# clock-temp-touch.net
KiCad netlist of a schematic drawn in Altium Designer
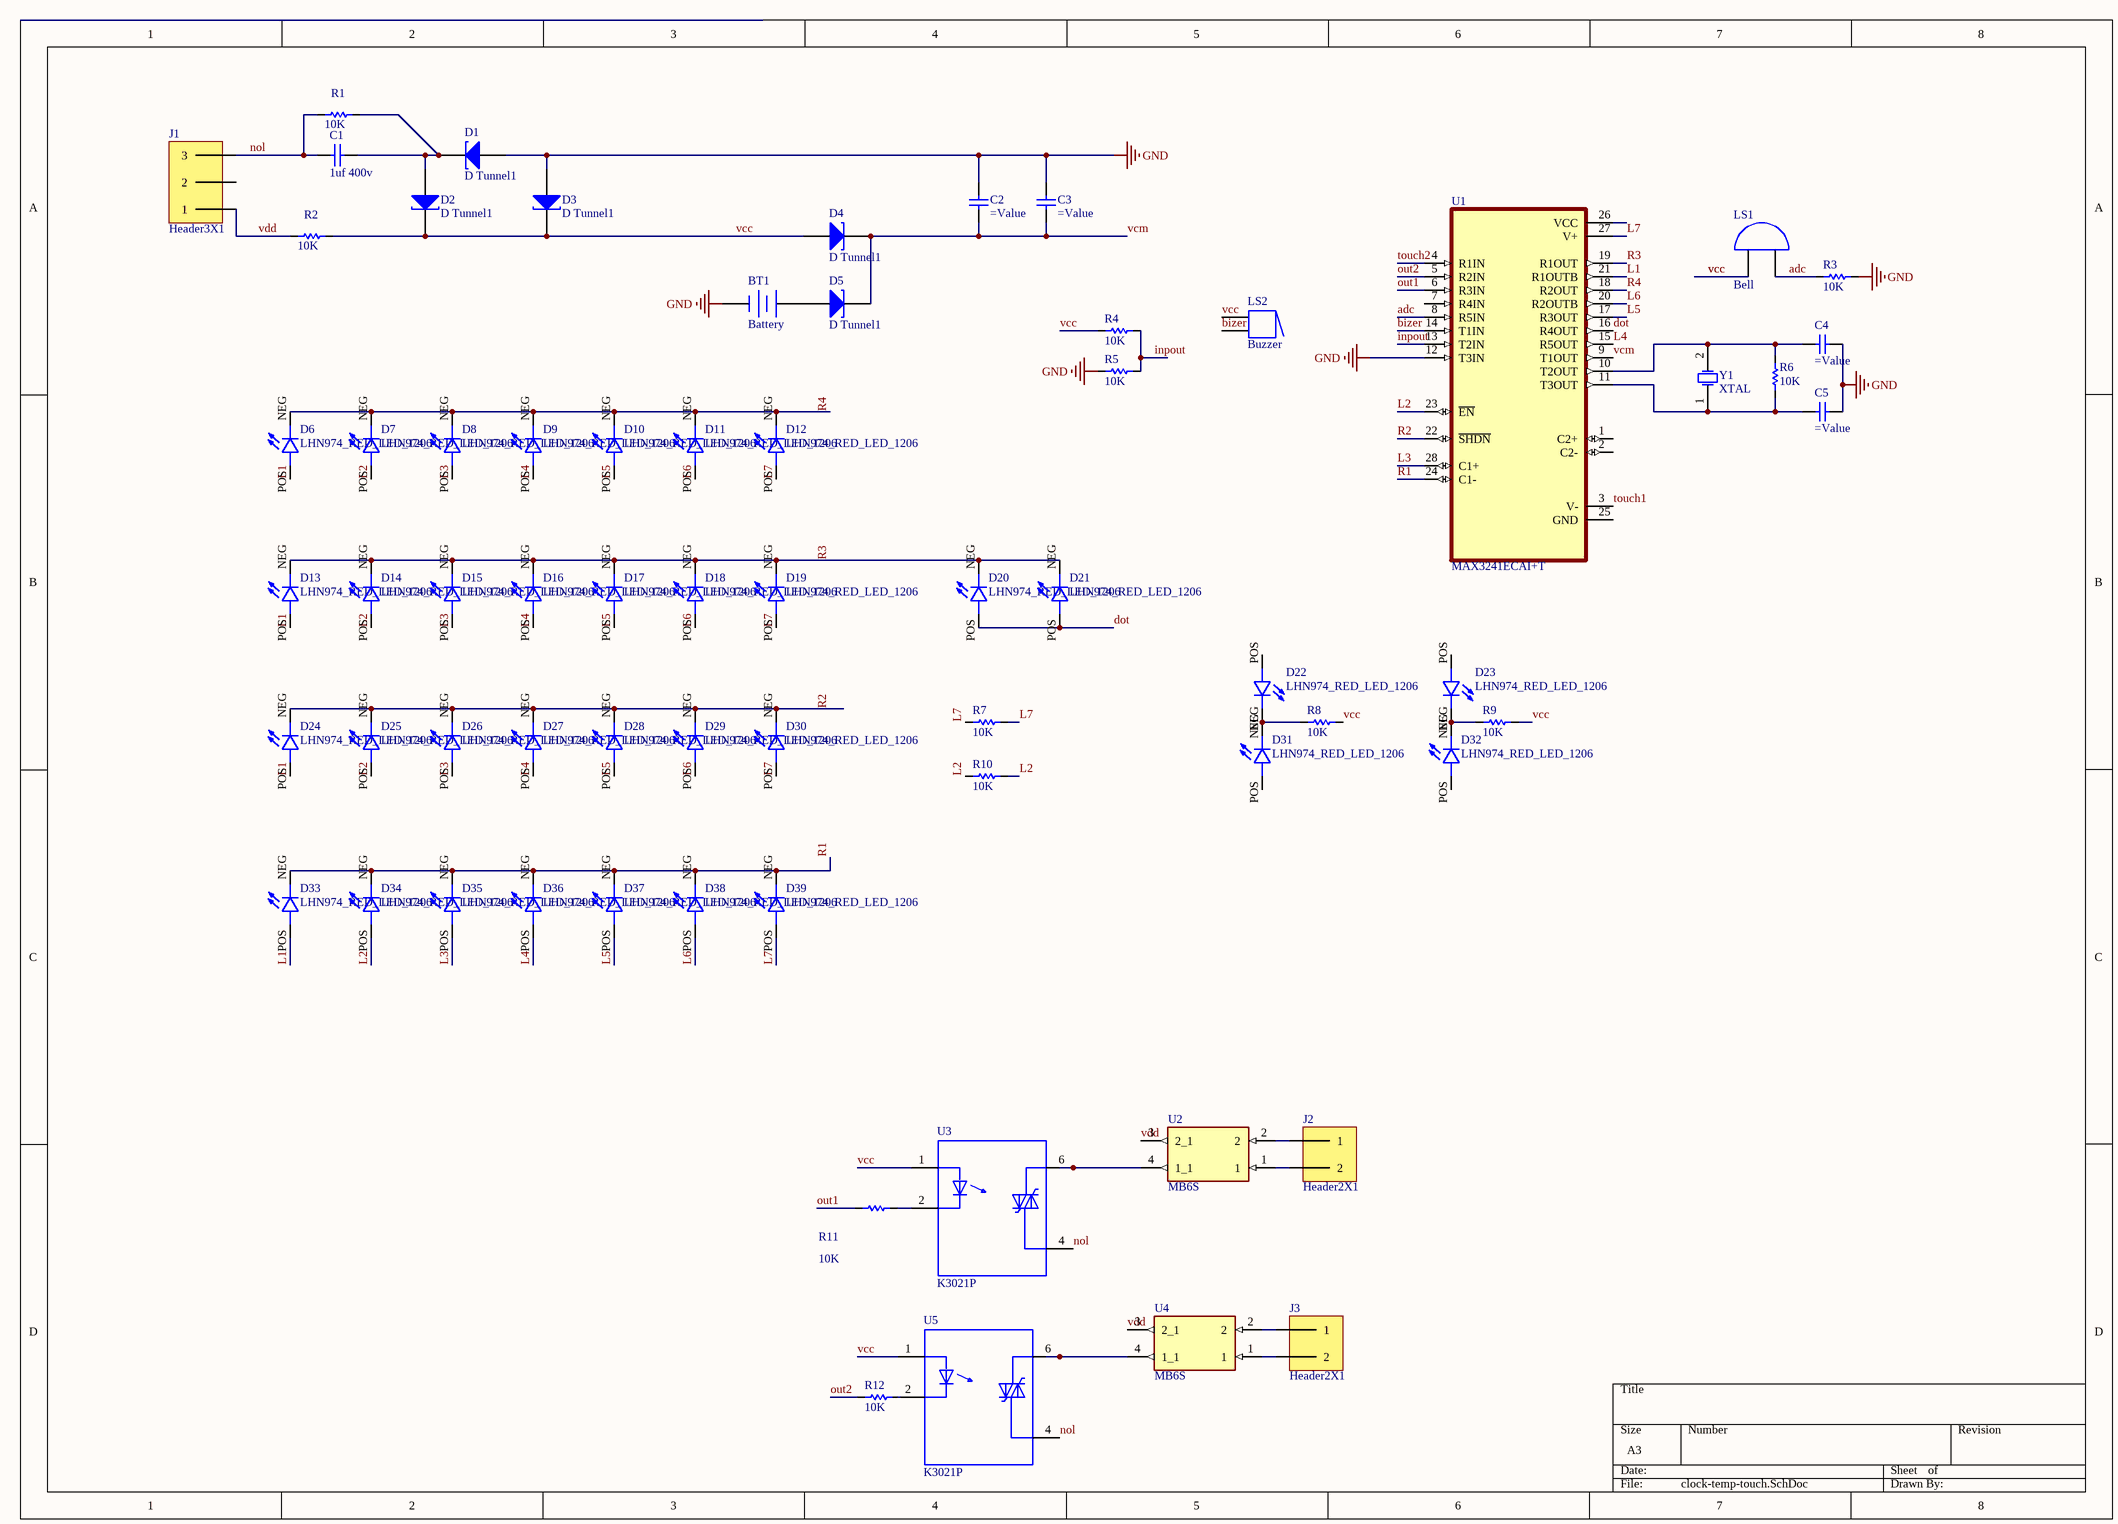
[diagram p0: clock-temp-touch.SchDoc]

(export (version "E")
  (design (tool "Eeschema 10.0.6"))
  (components
    (comp (ref "BT1")
      (value "Battery")
      (footprint "BAT-2")
      (description "Multicell Battery")
      (fields (field (name "PUBLISHER") "Altium Limited"))
      (libsource (lib "Miscellaneous Devices") (part "Battery"))
    )
    (comp (ref "C1")
      (value "1uf 400v")
      (footprint "1uf 400v")
      (description "Capacitor 24*9mm")
      (fields (field (name "DESIGNER") "Seyed Mohsen Ghasemain"))
      (libsource (lib "PicPars.com_usefully_Library") (part "1uf 400v"))
    )
    (comp (ref "C2")
      (value "~")
      (footprint "CAP 1206")
      (description "Capacitor")
      (libsource (lib "AltiumLib1") (part "Capacitor"))
    )
    (comp (ref "C3")
      (value "~")
      (footprint "CAP 1206")
      (description "Capacitor")
      (libsource (lib "AltiumLib1") (part "Capacitor"))
    )
    (comp (ref "C4")
      (value "~")
      (footprint "CAP 1206")
      (description "Capacitor")
      (libsource (lib "AltiumLib1") (part "Capacitor"))
    )
    (comp (ref "C5")
      (value "~")
      (footprint "CAP 1206")
      (description "Capacitor")
      (libsource (lib "AltiumLib1") (part "Capacitor"))
    )
    (comp (ref "D1")
      (value "D Tunnel1")
      (footprint "3.2X1.6X1.1")
      (description "Tunnel Diode - RLC Model")
      (fields (field (name "PUBLISHER") "Altium Limited"))
      (libsource (lib "Miscellaneous Devices") (part "D Tunnel1"))
    )
    (comp (ref "D2")
      (value "D Tunnel1")
      (footprint "3.2X1.6X1.1")
      (description "Tunnel Diode - RLC Model")
      (fields (field (name "PUBLISHER") "Altium Limited"))
      (libsource (lib "Miscellaneous Devices") (part "D Tunnel1"))
    )
    (comp (ref "D3")
      (value "D Tunnel1")
      (footprint "3.2X1.6X1.1")
      (description "Tunnel Diode - RLC Model")
      (fields (field (name "PUBLISHER") "Altium Limited"))
      (libsource (lib "Miscellaneous Devices") (part "D Tunnel1"))
    )
    (comp (ref "D4")
      (value "D Tunnel1")
      (footprint "3.2X1.6X1.1")
      (description "Tunnel Diode - RLC Model")
      (fields (field (name "PUBLISHER") "Altium Limited"))
      (libsource (lib "Miscellaneous Devices") (part "D Tunnel1"))
    )
    (comp (ref "D5")
      (value "D Tunnel1")
      (footprint "3.2X1.6X1.1")
      (description "Tunnel Diode - RLC Model")
      (fields (field (name "PUBLISHER") "Altium Limited"))
      (libsource (lib "Miscellaneous Devices") (part "D Tunnel1"))
    )
    (comp (ref "D6")
      (value "LHN974_RED_LED_1206")
      (footprint "LEDC3216X120N")
      (description "2.6 V Red LED SMD")
      (fields (field (name "MP") "LHN974 RED LED 1206") (field (name "MF") "Osram"))
      (libsource (lib "LHN974_RED_LED_1206") (part "LHN974_RED_LED_1206"))
    )
    (comp (ref "D7")
      (value "LHN974_RED_LED_1206")
      (footprint "LEDC3216X120N")
      (description "2.6 V Red LED SMD")
      (fields (field (name "MP") "LHN974 RED LED 1206") (field (name "MF") "Osram"))
      (libsource (lib "LHN974_RED_LED_1206") (part "LHN974_RED_LED_1206"))
    )
    (comp (ref "D8")
      (value "LHN974_RED_LED_1206")
      (footprint "LEDC3216X120N")
      (description "2.6 V Red LED SMD")
      (fields (field (name "MP") "LHN974 RED LED 1206") (field (name "MF") "Osram"))
      (libsource (lib "LHN974_RED_LED_1206") (part "LHN974_RED_LED_1206"))
    )
    (comp (ref "D9")
      (value "LHN974_RED_LED_1206")
      (footprint "LEDC3216X120N")
      (description "2.6 V Red LED SMD")
      (fields (field (name "MP") "LHN974 RED LED 1206") (field (name "MF") "Osram"))
      (libsource (lib "LHN974_RED_LED_1206") (part "LHN974_RED_LED_1206"))
    )
    (comp (ref "D10")
      (value "LHN974_RED_LED_1206")
      (footprint "LEDC3216X120N")
      (description "2.6 V Red LED SMD")
      (fields (field (name "MP") "LHN974 RED LED 1206") (field (name "MF") "Osram"))
      (libsource (lib "LHN974_RED_LED_1206") (part "LHN974_RED_LED_1206"))
    )
    (comp (ref "D11")
      (value "LHN974_RED_LED_1206")
      (footprint "LEDC3216X120N")
      (description "2.6 V Red LED SMD")
      (fields (field (name "MP") "LHN974 RED LED 1206") (field (name "MF") "Osram"))
      (libsource (lib "LHN974_RED_LED_1206") (part "LHN974_RED_LED_1206"))
    )
    (comp (ref "D12")
      (value "LHN974_RED_LED_1206")
      (footprint "LEDC3216X120N")
      (description "2.6 V Red LED SMD")
      (fields (field (name "MP") "LHN974 RED LED 1206") (field (name "MF") "Osram"))
      (libsource (lib "LHN974_RED_LED_1206") (part "LHN974_RED_LED_1206"))
    )
    (comp (ref "D13")
      (value "LHN974_RED_LED_1206")
      (footprint "LEDC3216X120N")
      (description "2.6 V Red LED SMD")
      (fields (field (name "MP") "LHN974 RED LED 1206") (field (name "MF") "Osram"))
      (libsource (lib "LHN974_RED_LED_1206") (part "LHN974_RED_LED_1206"))
    )
    (comp (ref "D14")
      (value "LHN974_RED_LED_1206")
      (footprint "LEDC3216X120N")
      (description "2.6 V Red LED SMD")
      (fields (field (name "MP") "LHN974 RED LED 1206") (field (name "MF") "Osram"))
      (libsource (lib "LHN974_RED_LED_1206") (part "LHN974_RED_LED_1206"))
    )
    (comp (ref "D15")
      (value "LHN974_RED_LED_1206")
      (footprint "LEDC3216X120N")
      (description "2.6 V Red LED SMD")
      (fields (field (name "MP") "LHN974 RED LED 1206") (field (name "MF") "Osram"))
      (libsource (lib "LHN974_RED_LED_1206") (part "LHN974_RED_LED_1206"))
    )
    (comp (ref "D16")
      (value "LHN974_RED_LED_1206")
      (footprint "LEDC3216X120N")
      (description "2.6 V Red LED SMD")
      (fields (field (name "MP") "LHN974 RED LED 1206") (field (name "MF") "Osram"))
      (libsource (lib "LHN974_RED_LED_1206") (part "LHN974_RED_LED_1206"))
    )
    (comp (ref "D17")
      (value "LHN974_RED_LED_1206")
      (footprint "LEDC3216X120N")
      (description "2.6 V Red LED SMD")
      (fields (field (name "MP") "LHN974 RED LED 1206") (field (name "MF") "Osram"))
      (libsource (lib "LHN974_RED_LED_1206") (part "LHN974_RED_LED_1206"))
    )
    (comp (ref "D18")
      (value "LHN974_RED_LED_1206")
      (footprint "LEDC3216X120N")
      (description "2.6 V Red LED SMD")
      (fields (field (name "MP") "LHN974 RED LED 1206") (field (name "MF") "Osram"))
      (libsource (lib "LHN974_RED_LED_1206") (part "LHN974_RED_LED_1206"))
    )
    (comp (ref "D19")
      (value "LHN974_RED_LED_1206")
      (footprint "LEDC3216X120N")
      (description "2.6 V Red LED SMD")
      (fields (field (name "MP") "LHN974 RED LED 1206") (field (name "MF") "Osram"))
      (libsource (lib "LHN974_RED_LED_1206") (part "LHN974_RED_LED_1206"))
    )
    (comp (ref "D20")
      (value "LHN974_RED_LED_1206")
      (footprint "LEDC3216X120N")
      (description "2.6 V Red LED SMD")
      (fields (field (name "MP") "LHN974 RED LED 1206") (field (name "MF") "Osram"))
      (libsource (lib "LHN974_RED_LED_1206") (part "LHN974_RED_LED_1206"))
    )
    (comp (ref "D21")
      (value "LHN974_RED_LED_1206")
      (footprint "LEDC3216X120N")
      (description "2.6 V Red LED SMD")
      (fields (field (name "MP") "LHN974 RED LED 1206") (field (name "MF") "Osram"))
      (libsource (lib "LHN974_RED_LED_1206") (part "LHN974_RED_LED_1206"))
    )
    (comp (ref "D22")
      (value "LHN974_RED_LED_1206")
      (footprint "LEDC3216X120N")
      (description "2.6 V Red LED SMD")
      (fields (field (name "MP") "LHN974 RED LED 1206") (field (name "MF") "Osram"))
      (libsource (lib "LHN974_RED_LED_1206") (part "LHN974_RED_LED_1206"))
    )
    (comp (ref "D23")
      (value "LHN974_RED_LED_1206")
      (footprint "LEDC3216X120N")
      (description "2.6 V Red LED SMD")
      (fields (field (name "MP") "LHN974 RED LED 1206") (field (name "MF") "Osram"))
      (libsource (lib "LHN974_RED_LED_1206") (part "LHN974_RED_LED_1206"))
    )
    (comp (ref "D24")
      (value "LHN974_RED_LED_1206")
      (footprint "LEDC3216X120N")
      (description "2.6 V Red LED SMD")
      (fields (field (name "MP") "LHN974 RED LED 1206") (field (name "MF") "Osram"))
      (libsource (lib "LHN974_RED_LED_1206") (part "LHN974_RED_LED_1206"))
    )
    (comp (ref "D25")
      (value "LHN974_RED_LED_1206")
      (footprint "LEDC3216X120N")
      (description "2.6 V Red LED SMD")
      (fields (field (name "MP") "LHN974 RED LED 1206") (field (name "MF") "Osram"))
      (libsource (lib "LHN974_RED_LED_1206") (part "LHN974_RED_LED_1206"))
    )
    (comp (ref "D26")
      (value "LHN974_RED_LED_1206")
      (footprint "LEDC3216X120N")
      (description "2.6 V Red LED SMD")
      (fields (field (name "MP") "LHN974 RED LED 1206") (field (name "MF") "Osram"))
      (libsource (lib "LHN974_RED_LED_1206") (part "LHN974_RED_LED_1206"))
    )
    (comp (ref "D27")
      (value "LHN974_RED_LED_1206")
      (footprint "LEDC3216X120N")
      (description "2.6 V Red LED SMD")
      (fields (field (name "MP") "LHN974 RED LED 1206") (field (name "MF") "Osram"))
      (libsource (lib "LHN974_RED_LED_1206") (part "LHN974_RED_LED_1206"))
    )
    (comp (ref "D28")
      (value "LHN974_RED_LED_1206")
      (footprint "LEDC3216X120N")
      (description "2.6 V Red LED SMD")
      (fields (field (name "MP") "LHN974 RED LED 1206") (field (name "MF") "Osram"))
      (libsource (lib "LHN974_RED_LED_1206") (part "LHN974_RED_LED_1206"))
    )
    (comp (ref "D29")
      (value "LHN974_RED_LED_1206")
      (footprint "LEDC3216X120N")
      (description "2.6 V Red LED SMD")
      (fields (field (name "MP") "LHN974 RED LED 1206") (field (name "MF") "Osram"))
      (libsource (lib "LHN974_RED_LED_1206") (part "LHN974_RED_LED_1206"))
    )
    (comp (ref "D30")
      (value "LHN974_RED_LED_1206")
      (footprint "LEDC3216X120N")
      (description "2.6 V Red LED SMD")
      (fields (field (name "MP") "LHN974 RED LED 1206") (field (name "MF") "Osram"))
      (libsource (lib "LHN974_RED_LED_1206") (part "LHN974_RED_LED_1206"))
    )
    (comp (ref "D31")
      (value "LHN974_RED_LED_1206")
      (footprint "LEDC3216X120N")
      (description "2.6 V Red LED SMD")
      (fields (field (name "MP") "LHN974 RED LED 1206") (field (name "MF") "Osram"))
      (libsource (lib "LHN974_RED_LED_1206") (part "LHN974_RED_LED_1206"))
    )
    (comp (ref "D32")
      (value "LHN974_RED_LED_1206")
      (footprint "LEDC3216X120N")
      (description "2.6 V Red LED SMD")
      (fields (field (name "MP") "LHN974 RED LED 1206") (field (name "MF") "Osram"))
      (libsource (lib "LHN974_RED_LED_1206") (part "LHN974_RED_LED_1206"))
    )
    (comp (ref "D33")
      (value "LHN974_RED_LED_1206")
      (footprint "LEDC3216X120N")
      (description "2.6 V Red LED SMD")
      (fields (field (name "MP") "LHN974 RED LED 1206") (field (name "MF") "Osram"))
      (libsource (lib "LHN974_RED_LED_1206") (part "LHN974_RED_LED_1206"))
    )
    (comp (ref "D34")
      (value "LHN974_RED_LED_1206")
      (footprint "LEDC3216X120N")
      (description "2.6 V Red LED SMD")
      (fields (field (name "MP") "LHN974 RED LED 1206") (field (name "MF") "Osram"))
      (libsource (lib "LHN974_RED_LED_1206") (part "LHN974_RED_LED_1206"))
    )
    (comp (ref "D35")
      (value "LHN974_RED_LED_1206")
      (footprint "LEDC3216X120N")
      (description "2.6 V Red LED SMD")
      (fields (field (name "MP") "LHN974 RED LED 1206") (field (name "MF") "Osram"))
      (libsource (lib "LHN974_RED_LED_1206") (part "LHN974_RED_LED_1206"))
    )
    (comp (ref "D36")
      (value "LHN974_RED_LED_1206")
      (footprint "LEDC3216X120N")
      (description "2.6 V Red LED SMD")
      (fields (field (name "MP") "LHN974 RED LED 1206") (field (name "MF") "Osram"))
      (libsource (lib "LHN974_RED_LED_1206") (part "LHN974_RED_LED_1206"))
    )
    (comp (ref "D37")
      (value "LHN974_RED_LED_1206")
      (footprint "LEDC3216X120N")
      (description "2.6 V Red LED SMD")
      (fields (field (name "MP") "LHN974 RED LED 1206") (field (name "MF") "Osram"))
      (libsource (lib "LHN974_RED_LED_1206") (part "LHN974_RED_LED_1206"))
    )
    (comp (ref "D38")
      (value "LHN974_RED_LED_1206")
      (footprint "LEDC3216X120N")
      (description "2.6 V Red LED SMD")
      (fields (field (name "MP") "LHN974 RED LED 1206") (field (name "MF") "Osram"))
      (libsource (lib "LHN974_RED_LED_1206") (part "LHN974_RED_LED_1206"))
    )
    (comp (ref "D39")
      (value "LHN974_RED_LED_1206")
      (footprint "LEDC3216X120N")
      (description "2.6 V Red LED SMD")
      (fields (field (name "MP") "LHN974 RED LED 1206") (field (name "MF") "Osram"))
      (libsource (lib "LHN974_RED_LED_1206") (part "LHN974_RED_LED_1206"))
    )
    (comp (ref "J1")
      (value "Header3X1")
      (footprint "HEADER 3X1")
      (libsource (lib "AltiumLib1") (part "Header3X1"))
    )
    (comp (ref "J2")
      (value "Header2X1")
      (footprint "Header 2X1")
      (libsource (lib "AltiumLib1") (part "Header2X1"))
    )
    (comp (ref "J3")
      (value "Header2X1")
      (footprint "Header 2X1")
      (libsource (lib "AltiumLib1") (part "Header2X1"))
    )
    (comp (ref "LS1")
      (value "Bell")
      (footprint "PIN2")
      (description "Electrical Bell")
      (fields (field (name "PUBLISHER") "Altium Limited"))
      (libsource (lib "Miscellaneous Devices") (part "Bell"))
    )
    (comp (ref "LS2")
      (value "Buzzer")
      (footprint "ABSM-1574")
      (description "Magnetic Transducer Buzzer")
      (fields (field (name "PUBLISHER") "Altium Limited"))
      (libsource (lib "Miscellaneous Devices") (part "Buzzer"))
    )
    (comp (ref "R1")
      (value "10K")
      (footprint "RES 1206 (3216X08L)")
      (description "Resistor")
      (fields (field (name "TOLERANCE") "5%") (field (name "POWER") "1/4 W"))
      (libsource (lib "AltiumLib1") (part "Resistor"))
    )
    (comp (ref "R2")
      (value "10K")
      (footprint "Res-(2/1)")
      (description "Resistor")
      (fields (field (name "TOLERANCE") "5%") (field (name "POWER") "1/4 W"))
      (libsource (lib "AltiumLib1") (part "Resistor"))
    )
    (comp (ref "R3")
      (value "10K")
      (footprint "RES 1206 (3216X08L)")
      (description "Resistor")
      (fields (field (name "TOLERANCE") "5%") (field (name "POWER") "1/4 W"))
      (libsource (lib "AltiumLib1") (part "Resistor"))
    )
    (comp (ref "R4")
      (value "10K")
      (footprint "RES 1206 (3216X08L)")
      (description "Resistor")
      (fields (field (name "TOLERANCE") "5%") (field (name "POWER") "1/4 W"))
      (libsource (lib "AltiumLib1") (part "Resistor"))
    )
    (comp (ref "R5")
      (value "10K")
      (footprint "RES 1206 (3216X08L)")
      (description "Resistor")
      (fields (field (name "TOLERANCE") "5%") (field (name "POWER") "1/4 W"))
      (libsource (lib "AltiumLib1") (part "Resistor"))
    )
    (comp (ref "R6")
      (value "10K")
      (footprint "RES 1206 (3216X08L)")
      (description "Resistor")
      (fields (field (name "TOLERANCE") "5%") (field (name "POWER") "1/4 W"))
      (libsource (lib "AltiumLib1") (part "Resistor"))
    )
    (comp (ref "R7")
      (value "10K")
      (footprint "RES 1206 (3216X08L)")
      (description "Resistor")
      (fields (field (name "TOLERANCE") "5%") (field (name "POWER") "1/4 W"))
      (libsource (lib "AltiumLib1") (part "Resistor"))
    )
    (comp (ref "R8")
      (value "10K")
      (footprint "RES 1206 (3216X08L)")
      (description "Resistor")
      (fields (field (name "TOLERANCE") "5%") (field (name "POWER") "1/4 W"))
      (libsource (lib "AltiumLib1") (part "Resistor"))
    )
    (comp (ref "R9")
      (value "10K")
      (footprint "RES 1206 (3216X08L)")
      (description "Resistor")
      (fields (field (name "TOLERANCE") "5%") (field (name "POWER") "1/4 W"))
      (libsource (lib "AltiumLib1") (part "Resistor"))
    )
    (comp (ref "R10")
      (value "10K")
      (footprint "RES 1206 (3216X08L)")
      (description "Resistor")
      (fields (field (name "TOLERANCE") "5%") (field (name "POWER") "1/4 W"))
      (libsource (lib "AltiumLib1") (part "Resistor"))
    )
    (comp (ref "R11")
      (value "10K")
      (footprint "RES 1206 (3216X08L)")
      (description "Resistor")
      (fields (field (name "TOLERANCE") "5%") (field (name "POWER") "1/4 W"))
      (libsource (lib "AltiumLib1") (part "Resistor"))
    )
    (comp (ref "R12")
      (value "10K")
      (footprint "RES 1206 (3216X08L)")
      (description "Resistor")
      (fields (field (name "TOLERANCE") "5%") (field (name "POWER") "1/4 W"))
      (libsource (lib "AltiumLib1") (part "Resistor"))
    )
    (comp (ref "U1")
      (value "MAX3241ECAI+T")
      (footprint "SOP65P777X199-28N")
      (description "±15kV ESD-Protected, Down to 10nA, 3.0V to 5.5V, Up to 1Mbps, True RS-232 Transceivers")
      (fields (field (name "MF") "Analog Devices"))
      (libsource (lib "ssop28") (part "MAX3241ECAI+T"))
    )
    (comp (ref "U2")
      (value "MB6S")
      (footprint "SOIC245P670X270-4N")
      (description "Bridge Rectifier Single Phase Standard 600V Surface Mount 4-SOIC")
      (fields (field (name "MF") "ON Semiconductor") (field (name "DIGI-KEY_PART_NUMBER") "MB6SCT-ND"))
      (libsource (lib "MB6S") (part "MB6S"))
    )
    (comp (ref "U3")
      (value "K3021P")
      (footprint "DIP762W50P254L730H410Q6")
      (description "Optoisolator Triac Output 5300Vrms 1 Channel 6-DIP")
      (fields (field (name "MF") "Vishay Semiconductor"))
      (libsource (lib "K3021P") (part "K3021P"))
    )
    (comp (ref "U4")
      (value "MB6S")
      (footprint "SOIC245P670X270-4N")
      (description "Bridge Rectifier Single Phase Standard 600V Surface Mount 4-SOIC")
      (fields (field (name "MF") "ON Semiconductor") (field (name "DIGI-KEY_PART_NUMBER") "MB6SCT-ND"))
      (libsource (lib "MB6S") (part "MB6S"))
    )
    (comp (ref "U5")
      (value "K3021P")
      (footprint "DIP762W50P254L730H410Q6")
      (description "Optoisolator Triac Output 5300Vrms 1 Channel 6-DIP")
      (fields (field (name "MF") "Vishay Semiconductor"))
      (libsource (lib "K3021P") (part "K3021P"))
    )
    (comp (ref "Y1")
      (value "XTAL")
      (footprint "R38")
      (description "Crystal Oscillator")
      (fields (field (name "PUBLISHER") "Altium Limited"))
      (libsource (lib "Miscellaneous Devices") (part "XTAL"))
    )
  )
  (nets
    (net (code "1") (name "/L1") (class "Default")
      (node (ref "D13") (pin "POS") (pinfunction "POS_POS") (pintype "passive"))
      (node (ref "D24") (pin "POS") (pinfunction "POS_POS") (pintype "passive"))
      (node (ref "D33") (pin "POS") (pinfunction "POS_POS") (pintype "passive"))
      (node (ref "D6") (pin "POS") (pinfunction "POS_POS") (pintype "passive"))
      (node (ref "U1") (pin "21") (pinfunction "R1OUTB_21") (pintype "output"))
    )
    (net (code "2") (name "/L2") (class "Default")
      (node (ref "D14") (pin "POS") (pinfunction "POS_POS") (pintype "passive"))
      (node (ref "D25") (pin "POS") (pinfunction "POS_POS") (pintype "passive"))
      (node (ref "D34") (pin "POS") (pinfunction "POS_POS") (pintype "passive"))
      (node (ref "D7") (pin "POS") (pinfunction "POS_POS") (pintype "passive"))
      (node (ref "R10") (pin "1") (pinfunction "1_1") (pintype "passive"))
      (node (ref "R10") (pin "2") (pinfunction "2_2") (pintype "passive"))
      (node (ref "U1") (pin "23") (pinfunction "~{EN}_23") (pintype "bidirectional"))
    )
    (net (code "3") (name "/L3") (class "Default")
      (node (ref "D15") (pin "POS") (pinfunction "POS_POS") (pintype "passive"))
      (node (ref "D26") (pin "POS") (pinfunction "POS_POS") (pintype "passive"))
      (node (ref "D35") (pin "POS") (pinfunction "POS_POS") (pintype "passive"))
      (node (ref "D8") (pin "POS") (pinfunction "POS_POS") (pintype "passive"))
      (node (ref "U1") (pin "28") (pinfunction "C1+_28") (pintype "bidirectional"))
    )
    (net (code "4") (name "/L4") (class "Default")
      (node (ref "D16") (pin "POS") (pinfunction "POS_POS") (pintype "passive"))
      (node (ref "D27") (pin "POS") (pinfunction "POS_POS") (pintype "passive"))
      (node (ref "D36") (pin "POS") (pinfunction "POS_POS") (pintype "passive"))
      (node (ref "D9") (pin "POS") (pinfunction "POS_POS") (pintype "passive"))
      (node (ref "U1") (pin "15") (pinfunction "R5OUT_15") (pintype "output"))
    )
    (net (code "5") (name "/L5") (class "Default")
      (node (ref "D10") (pin "POS") (pinfunction "POS_POS") (pintype "passive"))
      (node (ref "D17") (pin "POS") (pinfunction "POS_POS") (pintype "passive"))
      (node (ref "D28") (pin "POS") (pinfunction "POS_POS") (pintype "passive"))
      (node (ref "D37") (pin "POS") (pinfunction "POS_POS") (pintype "passive"))
      (node (ref "U1") (pin "17") (pinfunction "R3OUT_17") (pintype "output"))
    )
    (net (code "6") (name "/L6") (class "Default")
      (node (ref "D11") (pin "POS") (pinfunction "POS_POS") (pintype "passive"))
      (node (ref "D18") (pin "POS") (pinfunction "POS_POS") (pintype "passive"))
      (node (ref "D29") (pin "POS") (pinfunction "POS_POS") (pintype "passive"))
      (node (ref "D38") (pin "POS") (pinfunction "POS_POS") (pintype "passive"))
      (node (ref "U1") (pin "20") (pinfunction "R2OUTB_20") (pintype "output"))
    )
    (net (code "7") (name "/L7") (class "Default")
      (node (ref "D12") (pin "POS") (pinfunction "POS_POS") (pintype "passive"))
      (node (ref "D19") (pin "POS") (pinfunction "POS_POS") (pintype "passive"))
      (node (ref "D30") (pin "POS") (pinfunction "POS_POS") (pintype "passive"))
      (node (ref "D39") (pin "POS") (pinfunction "POS_POS") (pintype "passive"))
      (node (ref "R7") (pin "1") (pinfunction "1_1") (pintype "passive"))
      (node (ref "R7") (pin "2") (pinfunction "2_2") (pintype "passive"))
      (node (ref "U1") (pin "27") (pinfunction "V+_27") (pintype "power_in"))
    )
    (net (code "8") (name "/R1") (class "Default")
      (node (ref "D33") (pin "NEG") (pinfunction "NEG_NEG") (pintype "passive"))
      (node (ref "D34") (pin "NEG") (pinfunction "NEG_NEG") (pintype "passive"))
      (node (ref "D35") (pin "NEG") (pinfunction "NEG_NEG") (pintype "passive"))
      (node (ref "D36") (pin "NEG") (pinfunction "NEG_NEG") (pintype "passive"))
      (node (ref "D37") (pin "NEG") (pinfunction "NEG_NEG") (pintype "passive"))
      (node (ref "D38") (pin "NEG") (pinfunction "NEG_NEG") (pintype "passive"))
      (node (ref "D39") (pin "NEG") (pinfunction "NEG_NEG") (pintype "passive"))
      (node (ref "U1") (pin "24") (pinfunction "C1-_24") (pintype "bidirectional"))
    )
    (net (code "9") (name "/R2") (class "Default")
      (node (ref "D24") (pin "NEG") (pinfunction "NEG_NEG") (pintype "passive"))
      (node (ref "D25") (pin "NEG") (pinfunction "NEG_NEG") (pintype "passive"))
      (node (ref "D26") (pin "NEG") (pinfunction "NEG_NEG") (pintype "passive"))
      (node (ref "D27") (pin "NEG") (pinfunction "NEG_NEG") (pintype "passive"))
      (node (ref "D28") (pin "NEG") (pinfunction "NEG_NEG") (pintype "passive"))
      (node (ref "D29") (pin "NEG") (pinfunction "NEG_NEG") (pintype "passive"))
      (node (ref "D30") (pin "NEG") (pinfunction "NEG_NEG") (pintype "passive"))
      (node (ref "U1") (pin "22") (pinfunction "~{SHDN}_22") (pintype "bidirectional"))
    )
    (net (code "10") (name "/R3") (class "Default")
      (node (ref "D13") (pin "NEG") (pinfunction "NEG_NEG") (pintype "passive"))
      (node (ref "D14") (pin "NEG") (pinfunction "NEG_NEG") (pintype "passive"))
      (node (ref "D15") (pin "NEG") (pinfunction "NEG_NEG") (pintype "passive"))
      (node (ref "D16") (pin "NEG") (pinfunction "NEG_NEG") (pintype "passive"))
      (node (ref "D17") (pin "NEG") (pinfunction "NEG_NEG") (pintype "passive"))
      (node (ref "D18") (pin "NEG") (pinfunction "NEG_NEG") (pintype "passive"))
      (node (ref "D19") (pin "NEG") (pinfunction "NEG_NEG") (pintype "passive"))
      (node (ref "D20") (pin "NEG") (pinfunction "NEG_NEG") (pintype "passive"))
      (node (ref "D21") (pin "NEG") (pinfunction "NEG_NEG") (pintype "passive"))
      (node (ref "U1") (pin "19") (pinfunction "R1OUT_19") (pintype "output"))
    )
    (net (code "11") (name "/R4") (class "Default")
      (node (ref "D10") (pin "NEG") (pinfunction "NEG_NEG") (pintype "passive"))
      (node (ref "D11") (pin "NEG") (pinfunction "NEG_NEG") (pintype "passive"))
      (node (ref "D12") (pin "NEG") (pinfunction "NEG_NEG") (pintype "passive"))
      (node (ref "D6") (pin "NEG") (pinfunction "NEG_NEG") (pintype "passive"))
      (node (ref "D7") (pin "NEG") (pinfunction "NEG_NEG") (pintype "passive"))
      (node (ref "D8") (pin "NEG") (pinfunction "NEG_NEG") (pintype "passive"))
      (node (ref "D9") (pin "NEG") (pinfunction "NEG_NEG") (pintype "passive"))
      (node (ref "U1") (pin "18") (pinfunction "R2OUT_18") (pintype "output"))
    )
    (net (code "12") (name "/adc") (class "Default")
      (node (ref "LS1") (pin "2") (pinfunction "B_2") (pintype "passive"))
      (node (ref "R3") (pin "2") (pinfunction "2_2") (pintype "passive"))
      (node (ref "U1") (pin "8") (pinfunction "R5IN_8") (pintype "input"))
    )
    (net (code "13") (name "/bizer") (class "Default")
      (node (ref "LS2") (pin "2") (pinfunction "2_2") (pintype "passive"))
      (node (ref "LS2") (pin "2A") (pinfunction "2A_2A") (pintype "passive"))
      (node (ref "U1") (pin "14") (pinfunction "T1IN_14") (pintype "input"))
    )
    (net (code "14") (name "/dot") (class "Default")
      (node (ref "D20") (pin "POS") (pinfunction "POS_POS") (pintype "passive"))
      (node (ref "D21") (pin "POS") (pinfunction "POS_POS") (pintype "passive"))
      (node (ref "U1") (pin "16") (pinfunction "R4OUT_16") (pintype "output"))
    )
    (net (code "15") (name "/inpout") (class "Default")
      (node (ref "R4") (pin "1") (pinfunction "1_1") (pintype "passive"))
      (node (ref "R5") (pin "1") (pinfunction "1_1") (pintype "passive"))
      (node (ref "U1") (pin "13") (pinfunction "T2IN_13") (pintype "input"))
    )
    (net (code "16") (name "/nol") (class "Default")
      (node (ref "C1") (pin "1") (pinfunction "1_1") (pintype "passive"))
      (node (ref "J1") (pin "3") (pinfunction "3_3") (pintype "passive"))
      (node (ref "R1") (pin "1") (pinfunction "1_1") (pintype "passive"))
      (node (ref "U3") (pin "4") (pinfunction "MT1_4") (pintype "passive"))
      (node (ref "U5") (pin "4") (pinfunction "MT1_4") (pintype "passive"))
    )
    (net (code "17") (name "/out1") (class "Default")
      (node (ref "R11") (pin "2") (pinfunction "2_2") (pintype "passive"))
      (node (ref "U1") (pin "6") (pinfunction "R3IN_6") (pintype "input"))
    )
    (net (code "18") (name "/out2") (class "Default")
      (node (ref "R12") (pin "2") (pinfunction "2_2") (pintype "passive"))
      (node (ref "U1") (pin "5") (pinfunction "R2IN_5") (pintype "input"))
    )
    (net (code "19") (name "/touch1") (class "Default")
      (node (ref "U1") (pin "3") (pinfunction "V-_3") (pintype "power_in"))
    )
    (net (code "20") (name "/touch2") (class "Default")
      (node (ref "U1") (pin "4") (pinfunction "R1IN_4") (pintype "input"))
    )
    (net (code "21") (name "/vcc") (class "Default")
      (node (ref "D2") (pin "2") (pinfunction "K_2") (pintype "passive"))
      (node (ref "D3") (pin "2") (pinfunction "K_2") (pintype "passive"))
      (node (ref "D4") (pin "1") (pinfunction "A_1") (pintype "passive"))
      (node (ref "LS1") (pin "1") (pinfunction "A_1") (pintype "passive"))
      (node (ref "LS2") (pin "1") (pinfunction "1_1") (pintype "passive"))
      (node (ref "LS2") (pin "1A") (pinfunction "1A_1A") (pintype "passive"))
      (node (ref "R2") (pin "2") (pinfunction "2_2") (pintype "passive"))
      (node (ref "R4") (pin "2") (pinfunction "2_2") (pintype "passive"))
      (node (ref "R8") (pin "1") (pinfunction "1_1") (pintype "passive"))
      (node (ref "R9") (pin "1") (pinfunction "1_1") (pintype "passive"))
      (node (ref "U3") (pin "1") (pinfunction "A_1") (pintype "passive"))
      (node (ref "U5") (pin "1") (pinfunction "A_1") (pintype "passive"))
    )
    (net (code "22") (name "/vcm") (class "Default")
      (node (ref "C2") (pin "1") (pinfunction "+_1") (pintype "passive"))
      (node (ref "C3") (pin "1") (pinfunction "+_1") (pintype "passive"))
      (node (ref "D4") (pin "2") (pinfunction "K_2") (pintype "passive"))
      (node (ref "D5") (pin "2") (pinfunction "K_2") (pintype "passive"))
      (node (ref "U1") (pin "9") (pinfunction "T1OUT_9") (pintype "output"))
    )
    (net (code "23") (name "/vdd") (class "Default")
      (node (ref "J1") (pin "1") (pinfunction "1_1") (pintype "passive"))
      (node (ref "R2") (pin "1") (pinfunction "1_1") (pintype "passive"))
      (node (ref "U2") (pin "3") (pinfunction "2_1_3") (pintype "output"))
      (node (ref "U4") (pin "3") (pinfunction "2_1_3") (pintype "output"))
    )
    (net (code "24") (name "GND") (class "Default")
      (node (ref "BT1") (pin "2") (pinfunction "-_2") (pintype "passive"))
      (node (ref "C2") (pin "2") (pinfunction "-_2") (pintype "passive"))
      (node (ref "C3") (pin "2") (pinfunction "-_2") (pintype "passive"))
      (node (ref "C4") (pin "1") (pinfunction "+_1") (pintype "passive"))
      (node (ref "C5") (pin "1") (pinfunction "+_1") (pintype "passive"))
      (node (ref "D1") (pin "1") (pinfunction "A_1") (pintype "passive"))
      (node (ref "D3") (pin "1") (pinfunction "A_1") (pintype "passive"))
      (node (ref "R3") (pin "1") (pinfunction "1_1") (pintype "passive"))
      (node (ref "R5") (pin "2") (pinfunction "2_2") (pintype "passive"))
      (node (ref "U1") (pin "12") (pinfunction "T3IN_12") (pintype "input"))
    )
    (net (code "25") (name "Net-(BT1-+)") (class "Default")
      (node (ref "BT1") (pin "1") (pinfunction "+_1") (pintype "passive"))
      (node (ref "D5") (pin "1") (pinfunction "A_1") (pintype "passive"))
    )
    (net (code "26") (name "Net-(C4--)") (class "Default")
      (node (ref "C4") (pin "2") (pinfunction "-_2") (pintype "passive"))
      (node (ref "R6") (pin "2") (pinfunction "2_2") (pintype "passive"))
      (node (ref "U1") (pin "10") (pinfunction "T2OUT_10") (pintype "output"))
      (node (ref "Y1") (pin "2") (pinfunction "OSC2_2") (pintype "passive"))
    )
    (net (code "27") (name "Net-(C5--)") (class "Default")
      (node (ref "C5") (pin "2") (pinfunction "-_2") (pintype "passive"))
      (node (ref "R6") (pin "1") (pinfunction "1_1") (pintype "passive"))
      (node (ref "U1") (pin "11") (pinfunction "T3OUT_11") (pintype "output"))
      (node (ref "Y1") (pin "1") (pinfunction "OSC1_1") (pintype "passive"))
    )
    (net (code "28") (name "Net-(D1-K)") (class "Default")
      (node (ref "C1") (pin "2") (pinfunction "2_2") (pintype "passive"))
      (node (ref "D1") (pin "2") (pinfunction "K_2") (pintype "passive"))
      (node (ref "D2") (pin "1") (pinfunction "A_1") (pintype "passive"))
      (node (ref "R1") (pin "2") (pinfunction "2_2") (pintype "passive"))
    )
    (net (code "29") (name "Net-(D22-PadNEG)") (class "Default")
      (node (ref "D22") (pin "NEG") (pinfunction "NEG_NEG") (pintype "passive"))
      (node (ref "D31") (pin "NEG") (pinfunction "NEG_NEG") (pintype "passive"))
      (node (ref "R8") (pin "2") (pinfunction "2_2") (pintype "passive"))
    )
    (net (code "30") (name "Net-(D23-PadNEG)") (class "Default")
      (node (ref "D23") (pin "NEG") (pinfunction "NEG_NEG") (pintype "passive"))
      (node (ref "D32") (pin "NEG") (pinfunction "NEG_NEG") (pintype "passive"))
      (node (ref "R9") (pin "2") (pinfunction "2_2") (pintype "passive"))
    )
    (net (code "31") (name "Net-(J2-Pad1)") (class "Default")
      (node (ref "J2") (pin "1") (pinfunction "1_1") (pintype "passive"))
      (node (ref "U2") (pin "2") (pinfunction "2_2") (pintype "input"))
    )
    (net (code "32") (name "Net-(J2-Pad2)") (class "Default")
      (node (ref "J2") (pin "2") (pinfunction "2_2") (pintype "passive"))
      (node (ref "U2") (pin "1") (pinfunction "1_1") (pintype "input"))
    )
    (net (code "33") (name "Net-(J3-Pad1)") (class "Default")
      (node (ref "J3") (pin "1") (pinfunction "1_1") (pintype "passive"))
      (node (ref "U4") (pin "2") (pinfunction "2_2") (pintype "input"))
    )
    (net (code "34") (name "Net-(J3-Pad2)") (class "Default")
      (node (ref "J3") (pin "2") (pinfunction "2_2") (pintype "passive"))
      (node (ref "U4") (pin "1") (pinfunction "1_1") (pintype "input"))
    )
    (net (code "35") (name "Net-(U2-1_1)") (class "Default")
      (node (ref "U2") (pin "4") (pinfunction "1_1_4") (pintype "output"))
      (node (ref "U3") (pin "6") (pinfunction "MT2_6") (pintype "passive"))
    )
    (net (code "36") (name "Net-(U3-C)") (class "Default")
      (node (ref "R11") (pin "1") (pinfunction "1_1") (pintype "passive"))
      (node (ref "U3") (pin "2") (pinfunction "C_2") (pintype "passive"))
    )
    (net (code "37") (name "Net-(U4-1_1)") (class "Default")
      (node (ref "U4") (pin "4") (pinfunction "1_1_4") (pintype "output"))
      (node (ref "U5") (pin "6") (pinfunction "MT2_6") (pintype "passive"))
    )
    (net (code "38") (name "Net-(U5-C)") (class "Default")
      (node (ref "R12") (pin "1") (pinfunction "1_1") (pintype "passive"))
      (node (ref "U5") (pin "2") (pinfunction "C_2") (pintype "passive"))
    )
    (net (code "39") (name "unconnected-(D22-PadPOS)") (class "Default")
      (node (ref "D22") (pin "POS") (pinfunction "POS_POS") (pintype "passive"))
    )
    (net (code "40") (name "unconnected-(D23-PadPOS)") (class "Default")
      (node (ref "D23") (pin "POS") (pinfunction "POS_POS") (pintype "passive"))
    )
    (net (code "41") (name "unconnected-(D31-PadPOS)") (class "Default")
      (node (ref "D31") (pin "POS") (pinfunction "POS_POS") (pintype "passive"))
    )
    (net (code "42") (name "unconnected-(D32-PadPOS)") (class "Default")
      (node (ref "D32") (pin "POS") (pinfunction "POS_POS") (pintype "passive"))
    )
    (net (code "43") (name "unconnected-(J1-Pad2)") (class "Default")
      (node (ref "J1") (pin "2") (pinfunction "2_2") (pintype "passive"))
    )
    (net (code "44") (name "unconnected-(U1-C2+-Pad1)") (class "Default")
      (node (ref "U1") (pin "1") (pinfunction "C2+_1") (pintype "bidirectional"))
    )
    (net (code "45") (name "unconnected-(U1-C2--Pad2)") (class "Default")
      (node (ref "U1") (pin "2") (pinfunction "C2-_2") (pintype "bidirectional"))
    )
    (net (code "46") (name "unconnected-(U1-GND-Pad25)") (class "Default")
      (node (ref "U1") (pin "25") (pinfunction "GND_25") (pintype "power_in"))
    )
    (net (code "47") (name "unconnected-(U1-R4IN-Pad7)") (class "Default")
      (node (ref "U1") (pin "7") (pinfunction "R4IN_7") (pintype "input"))
    )
    (net (code "48") (name "unconnected-(U1-VCC-Pad26)") (class "Default")
      (node (ref "U1") (pin "26") (pinfunction "VCC_26") (pintype "power_in"))
    )
  )
)
